# Preamp.net
KiCad netlist of a schematic drawn in Altium Designer
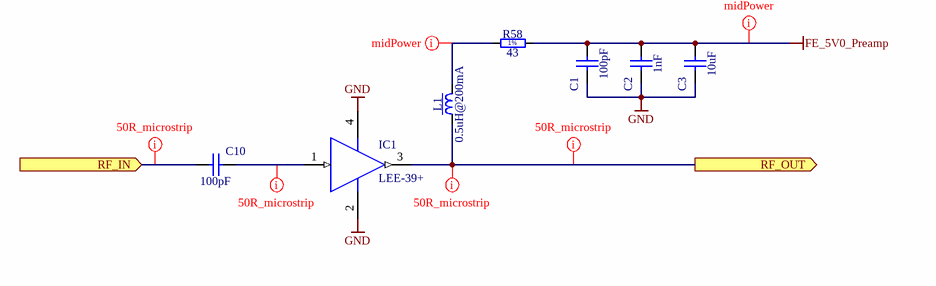
[diagram p0: Preamp.SchDoc]

(export (version "E")
  (design (tool "Eeschema 10.0.6"))
  (components
    (comp (ref "C1")
      (value "100pF")
      (footprint "CAPC1005X55N")
      (description "Non-polarised capacitor")
      (fields
        (field (name "PART NUMBER") "CC0402_100PF_50V_5%_C0G")
        (field (name "VOLTAGE") "50V")
        (field (name "AUTHOR") "CERN DEM JLC")
      )
      (libsource (lib "Capacitors") (part "Capacitor - non polarized"))
    )
    (comp (ref "C2")
      (value "1nF")
      (footprint "CAPC1005X55N")
      (description "Non-polarised capacitor")
      (fields
        (field (name "PART NUMBER") "CC0402_1NF_50V_10%_X7R")
        (field (name "VOLTAGE") "50V")
        (field (name "AUTHOR") "CERN DEM JLC")
      )
      (libsource (lib "Capacitors") (part "Capacitor - non polarized"))
    )
    (comp (ref "C3")
      (value "10uF")
      (footprint "CAPC3216X180N")
      (description "Non-polarised capacitor")
      (fields
        (field (name "PART NUMBER") "CC1206_10UF_25V_10%_X7R")
        (field (name "VOLTAGE") "25V")
        (field (name "AUTHOR") "CERN DEM JLC")
      )
      (libsource (lib "Capacitors") (part "Capacitor - non polarized"))
    )
    (comp (ref "C10")
      (value "100pF")
      (footprint "CAPC1005X55N")
      (description "Non-polarised capacitor")
      (fields
        (field (name "PART NUMBER") "CC0402_100PF_50V_5%_C0G")
        (field (name "VOLTAGE") "50V")
        (field (name "AUTHOR") "CERN DEM JLC")
      )
      (libsource (lib "Capacitors") (part "Capacitor - non polarized"))
    )
    (comp (ref "IC1")
      (value "LEE-39+")
      (footprint "MINI-CIRCUITS_FG873")
      (description "Monolithic Amplifier")
      (fields (field (name "MANUFACTURER") "MINI-CIRCUITS") (field (name "AUTHOR") "CERN DEM JLC"))
      (libsource (lib "ICs And Semiconductors") (part "Monolithic Amplifier Type 1"))
    )
    (comp (ref "L1")
      (value "0.5uH@200mA")
      (footprint "IND_MINI-CIRCUITS_GU1604")
      (description "50 Ohms, 50 to 8200 MHz RF Choke")
      (fields
        (field (name "PART NUMBER") "IND_MINI-CIRCUITS_TCCH-80+")
        (field (name "POWER") "200mA")
        (field (name "AUTHOR") "CERN DEM JLC")
      )
      (libsource (lib "Inductors & Transformers") (part "IND_MINI-CIRCUITS_TCCH-80+"))
    )
    (comp (ref "R58")
      (value "43")
      (footprint "RESC1608X55N")
      (description "Resistor - 1%")
      (fields
        (field (name "PART NUMBER") "R0603_43R_1%_0.1W_100PPM")
        (field (name "POWER") "0.1W")
        (field (name "AUTHOR") "CERN DEM JLC")
      )
      (libsource (lib "Resistors") (part "Resistor - 1%"))
    )
  )
  (nets
    (net (code "1") (name "/RF_IN") (class "Default")
      (node (ref "C10") (pin "1") (pinfunction "1_1") (pintype "passive"))
    )
    (net (code "2") (name "/RF_OUT") (class "Default")
      (node (ref "IC1") (pin "3") (pinfunction "RF_OUT_3") (pintype "output"))
      (node (ref "L1") (pin "1") (pinfunction "1_1") (pintype "passive"))
    )
    (net (code "3") (name "FE_5V0_Preamp") (class "Default")
      (node (ref "C1") (pin "2") (pinfunction "2_2") (pintype "passive"))
      (node (ref "C2") (pin "2") (pinfunction "2_2") (pintype "passive"))
      (node (ref "C3") (pin "2") (pinfunction "2_2") (pintype "passive"))
      (node (ref "R58") (pin "2") (pinfunction "2_2") (pintype "passive"))
    )
    (net (code "4") (name "GND") (class "Default")
      (node (ref "C1") (pin "1") (pinfunction "1_1") (pintype "passive"))
      (node (ref "C2") (pin "1") (pinfunction "1_1") (pintype "passive"))
      (node (ref "C3") (pin "1") (pinfunction "1_1") (pintype "passive"))
      (node (ref "IC1") (pin "2") (pinfunction "GND_2") (pintype "power_in"))
      (node (ref "IC1") (pin "4") (pinfunction "GND_4") (pintype "power_in"))
    )
    (net (code "5") (name "Net-(IC1-RF_IN)") (class "Default")
      (node (ref "C10") (pin "2") (pinfunction "2_2") (pintype "passive"))
      (node (ref "IC1") (pin "1") (pinfunction "RF_IN_1") (pintype "input"))
    )
    (net (code "6") (name "Net-(L1-Pad3)") (class "Default")
      (node (ref "L1") (pin "3") (pinfunction "3_3") (pintype "passive"))
      (node (ref "R58") (pin "1") (pinfunction "1_1") (pintype "passive"))
    )
  )
)
